# SSRSheet.net
KiCad netlist of a schematic drawn in Altium Designer
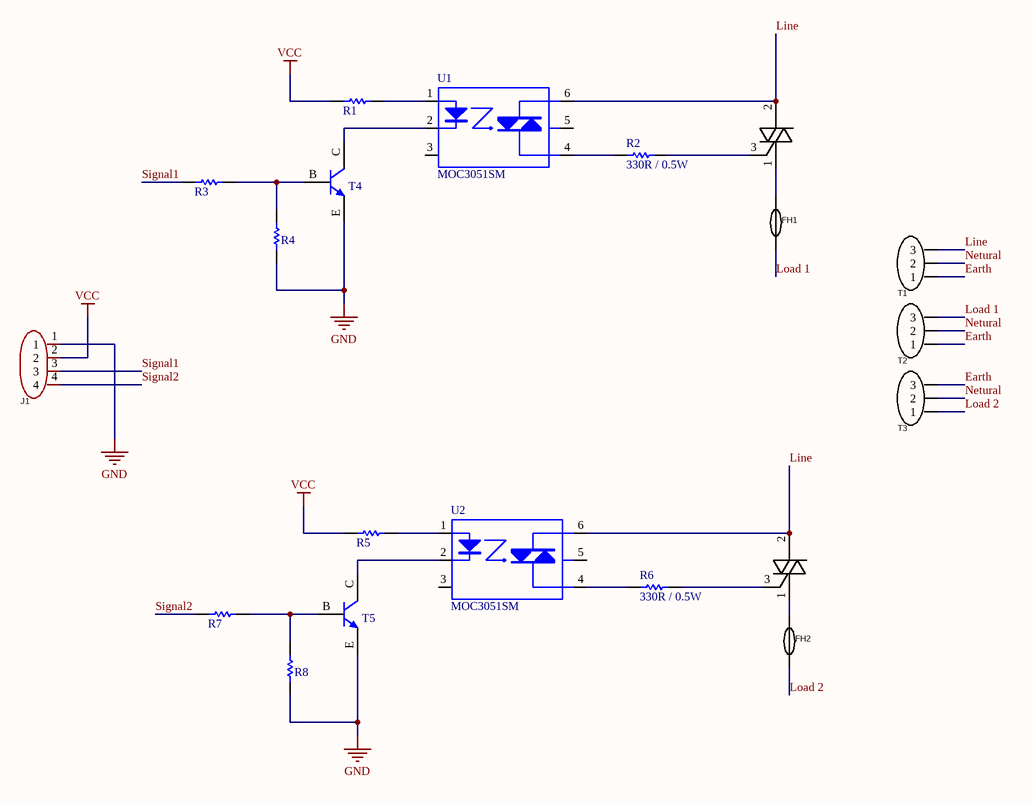
[diagram p0: SSRSheet.SchDoc]

(export (version "E")
  (design (tool "Eeschema 10.0.6"))
  (components
    (comp (ref "FH1")
      (value "XF-154")
      (footprint "FUSE-SMD_L10.5-W5.1")
      (description "C41371861")
      (fields (field (name "MANUFACTURER") "XFCN(兴飞)"))
      (libsource (lib "DIVERSE") (part "XF-154"))
    )
    (comp (ref "FH2")
      (value "XF-154")
      (footprint "FUSE-SMD_L10.5-W5.1")
      (description "C41371861")
      (fields (field (name "MANUFACTURER") "XFCN(兴飞)"))
      (libsource (lib "DIVERSE") (part "XF-154"))
    )
    (comp (ref "J1")
      (value "Header 4P*2mm")
      (footprint "CONN-TH_4P-P2.00_HX20020-4A_2")
      (description "C541313")
      (fields (field (name "MANUFACTURER") "Megastar(兆星)") (field (name "MANUFACTURER PART") "ZX-HY2.0-4PZZ"))
      (libsource (lib "LIB") (part "ZX-HY2.0-4PZZ"))
    )
    (comp (ref "Q1")
      (value "BT136S-800E,118")
      (footprint "TO-252-3_L6.6-W6.1-P4.57-LS9.9-BR-CW")
      (description "C581422")
      (fields (field (name "MANUFACTURER") "WeEn(瑞能)"))
      (libsource (lib "DIVERSE") (part "BT136S-800E,118"))
    )
    (comp (ref "Q2")
      (value "BT136S-800E,118")
      (footprint "TO-252-3_L6.6-W6.1-P4.57-LS9.9-BR-CW")
      (description "C581422")
      (fields (field (name "MANUFACTURER") "WeEn(瑞能)"))
      (libsource (lib "DIVERSE") (part "BT136S-800E,118"))
    )
    (comp (ref "R1")
      (value "330R")
      (footprint "R0402")
      (description "C159971")
      (libsource (lib "DIVERSE") (part "0402 Resistor"))
    )
    (comp (ref "R2")
      (value "330R / 0.5W")
      (footprint "R1210")
      (description "C2933817")
      (fields
        (field (name "MANUFACTURER") "Yageo")
        (field (name "MANUFACTURER PART NUMBER") "AC1210FR-07330RL")
      )
      (libsource (lib "Azan_Lib") (part "AC1210FR-07330RL"))
    )
    (comp (ref "R3")
      (value "4.7kR")
      (footprint "R0402")
      (description "C105871")
      (libsource (lib "DIVERSE") (part "0402 Resistor"))
    )
    (comp (ref "R4")
      (value "10kR")
      (footprint "R0402")
      (description "C60490")
      (libsource (lib "DIVERSE") (part "0402 Resistor"))
    )
    (comp (ref "R5")
      (value "330R")
      (footprint "R0402")
      (description "C159971")
      (libsource (lib "DIVERSE") (part "0402 Resistor"))
    )
    (comp (ref "R6")
      (value "330R / 0.5W")
      (footprint "R1210")
      (description "C2933817")
      (fields
        (field (name "MANUFACTURER") "Yageo")
        (field (name "MANUFACTURER PART NUMBER") "AC1210FR-07330RL")
      )
      (libsource (lib "Azan_Lib") (part "AC1210FR-07330RL"))
    )
    (comp (ref "R7")
      (value "4.7kR")
      (footprint "R0402")
      (description "C105871")
      (libsource (lib "DIVERSE") (part "0402 Resistor"))
    )
    (comp (ref "R8")
      (value "10kR")
      (footprint "R0402")
      (description "C60490")
      (libsource (lib "DIVERSE") (part "0402 Resistor"))
    )
    (comp (ref "T1")
      (value "WJ45C-B-9.5-3P")
      (footprint "CONN-TH_3P-P9.50_WJ45C-B-3P")
      (description "C8442")
      (fields (field (name "MANUFACTURER") "KANGNEX(康奈克斯电气)"))
      (libsource (lib "DIVERSE") (part "WJ45C-B-9.5-3P"))
    )
    (comp (ref "T2")
      (value "WJ45C-B-9.5-3P")
      (footprint "CONN-TH_3P-P9.50_WJ45C-B-3P")
      (description "C8442")
      (fields (field (name "MANUFACTURER") "KANGNEX(康奈克斯电气)"))
      (libsource (lib "DIVERSE") (part "WJ45C-B-9.5-3P"))
    )
    (comp (ref "T3")
      (value "WJ45C-B-9.5-3P")
      (footprint "CONN-TH_3P-P9.50_WJ45C-B-3P")
      (description "C8442")
      (fields (field (name "MANUFACTURER") "KANGNEX(康奈克斯电气)"))
      (libsource (lib "DIVERSE") (part "WJ45C-B-9.5-3P"))
    )
    (comp (ref "T4")
      (value "MMBT3904 Transistor")
      (footprint "MMBT3904")
      (description "C181119")
      (fields (field (name "CREATED BY") "NourAldin"))
      (libsource (lib "MMBT3904 Transistor") (part "MMBT3904 Transistor"))
    )
    (comp (ref "T5")
      (value "MMBT3904 Transistor")
      (footprint "MMBT3904")
      (description "C181119")
      (fields (field (name "CREATED BY") "NourAldin"))
      (libsource (lib "MMBT3904 Transistor") (part "MMBT3904 Transistor"))
    )
    (comp (ref "U1")
      (value "MOC3051SM")
      (footprint "OPTOTRIAC_SMD_6PIN")
      (description "C22373368")
      (fields (field (name "MANUFACTURER") "ON Semiconductor / Fairchild"))
      (libsource (lib "Azan_Lib") (part "MOC3051SM"))
    )
    (comp (ref "U2")
      (value "MOC3051SM")
      (footprint "OPTOTRIAC_SMD_6PIN")
      (description "C22373368")
      (fields (field (name "MANUFACTURER") "ON Semiconductor / Fairchild"))
      (libsource (lib "Azan_Lib") (part "MOC3051SM"))
    )
  )
  (nets
    (net (code "1") (name "/Earth") (class "Default")
      (node (ref "T1") (pin "1") (pinfunction "1_1") (pintype "passive"))
      (node (ref "T2") (pin "1") (pinfunction "1_1") (pintype "passive"))
      (node (ref "T3") (pin "3") (pinfunction "3_3") (pintype "passive"))
    )
    (net (code "2") (name "/Line") (class "Default")
      (node (ref "Q1") (pin "2") (pinfunction "T2_2") (pintype "passive"))
      (node (ref "Q2") (pin "2") (pinfunction "T2_2") (pintype "passive"))
      (node (ref "T1") (pin "3") (pinfunction "3_3") (pintype "passive"))
      (node (ref "U1") (pin "6") (pinfunction "6_6") (pintype "passive"))
      (node (ref "U2") (pin "6") (pinfunction "6_6") (pintype "passive"))
    )
    (net (code "3") (name "/Load 1") (class "Default")
      (node (ref "FH1") (pin "1") (pinfunction "1_1") (pintype "passive"))
      (node (ref "T2") (pin "3") (pinfunction "3_3") (pintype "passive"))
    )
    (net (code "4") (name "/Load 2") (class "Default")
      (node (ref "FH2") (pin "1") (pinfunction "1_1") (pintype "passive"))
      (node (ref "T3") (pin "1") (pinfunction "1_1") (pintype "passive"))
    )
    (net (code "5") (name "/Netural") (class "Default")
      (node (ref "T1") (pin "2") (pinfunction "2_2") (pintype "passive"))
      (node (ref "T2") (pin "2") (pinfunction "2_2") (pintype "passive"))
      (node (ref "T3") (pin "2") (pinfunction "2_2") (pintype "passive"))
    )
    (net (code "6") (name "/Signal1") (class "Default")
      (node (ref "J1") (pin "3") (pinfunction "3_3") (pintype "passive"))
      (node (ref "R3") (pin "1") (pinfunction "1_1") (pintype "passive"))
    )
    (net (code "7") (name "/Signal2") (class "Default")
      (node (ref "J1") (pin "4") (pinfunction "4_4") (pintype "passive"))
      (node (ref "R7") (pin "1") (pinfunction "1_1") (pintype "passive"))
    )
    (net (code "8") (name "GND") (class "Default")
      (node (ref "J1") (pin "1") (pinfunction "1_1") (pintype "passive"))
      (node (ref "R4") (pin "1") (pinfunction "1_1") (pintype "passive"))
      (node (ref "R8") (pin "1") (pinfunction "1_1") (pintype "passive"))
      (node (ref "T4") (pin "E") (pinfunction "E_E") (pintype "passive"))
      (node (ref "T5") (pin "E") (pinfunction "E_E") (pintype "passive"))
    )
    (net (code "9") (name "Net-(Q1-G)") (class "Default")
      (node (ref "Q1") (pin "3") (pinfunction "G_3") (pintype "passive"))
      (node (ref "R2") (pin "1") (pinfunction "1_1") (pintype "passive"))
    )
    (net (code "10") (name "Net-(Q1-T1)") (class "Default")
      (node (ref "FH1") (pin "2") (pinfunction "2_2") (pintype "passive"))
      (node (ref "Q1") (pin "1") (pinfunction "T1_1") (pintype "passive"))
    )
    (net (code "11") (name "Net-(Q2-G)") (class "Default")
      (node (ref "Q2") (pin "3") (pinfunction "G_3") (pintype "passive"))
      (node (ref "R6") (pin "1") (pinfunction "1_1") (pintype "passive"))
    )
    (net (code "12") (name "Net-(Q2-T1)") (class "Default")
      (node (ref "FH2") (pin "2") (pinfunction "2_2") (pintype "passive"))
      (node (ref "Q2") (pin "1") (pinfunction "T1_1") (pintype "passive"))
    )
    (net (code "13") (name "Net-(R1-Pad2)") (class "Default")
      (node (ref "R1") (pin "2") (pinfunction "2_2") (pintype "passive"))
      (node (ref "U1") (pin "1") (pinfunction "1_1") (pintype "passive"))
    )
    (net (code "14") (name "Net-(R2-Pad2)") (class "Default")
      (node (ref "R2") (pin "2") (pinfunction "2_2") (pintype "passive"))
      (node (ref "U1") (pin "4") (pinfunction "4_4") (pintype "passive"))
    )
    (net (code "15") (name "Net-(R3-Pad2)") (class "Default")
      (node (ref "R3") (pin "2") (pinfunction "2_2") (pintype "passive"))
      (node (ref "R4") (pin "2") (pinfunction "2_2") (pintype "passive"))
      (node (ref "T4") (pin "B") (pinfunction "B_B") (pintype "passive"))
    )
    (net (code "16") (name "Net-(R5-Pad2)") (class "Default")
      (node (ref "R5") (pin "2") (pinfunction "2_2") (pintype "passive"))
      (node (ref "U2") (pin "1") (pinfunction "1_1") (pintype "passive"))
    )
    (net (code "17") (name "Net-(R6-Pad2)") (class "Default")
      (node (ref "R6") (pin "2") (pinfunction "2_2") (pintype "passive"))
      (node (ref "U2") (pin "4") (pinfunction "4_4") (pintype "passive"))
    )
    (net (code "18") (name "Net-(R7-Pad2)") (class "Default")
      (node (ref "R7") (pin "2") (pinfunction "2_2") (pintype "passive"))
      (node (ref "R8") (pin "2") (pinfunction "2_2") (pintype "passive"))
      (node (ref "T5") (pin "B") (pinfunction "B_B") (pintype "passive"))
    )
    (net (code "19") (name "Net-(T4-PadC)") (class "Default")
      (node (ref "T4") (pin "C") (pinfunction "C_C") (pintype "passive"))
      (node (ref "U1") (pin "2") (pinfunction "2_2") (pintype "passive"))
    )
    (net (code "20") (name "Net-(T5-PadC)") (class "Default")
      (node (ref "T5") (pin "C") (pinfunction "C_C") (pintype "passive"))
      (node (ref "U2") (pin "2") (pinfunction "2_2") (pintype "passive"))
    )
    (net (code "21") (name "VCC") (class "Default")
      (node (ref "J1") (pin "2") (pinfunction "2_2") (pintype "passive"))
      (node (ref "R1") (pin "1") (pinfunction "1_1") (pintype "passive"))
      (node (ref "R5") (pin "1") (pinfunction "1_1") (pintype "passive"))
    )
    (net (code "22") (name "unconnected-(U1-NC_1-Pad3)") (class "Default")
      (node (ref "U1") (pin "3") (pinfunction "NC_1_3") (pintype "passive"))
    )
    (net (code "23") (name "unconnected-(U1-NC_2-Pad5)") (class "Default")
      (node (ref "U1") (pin "5") (pinfunction "NC_2_5") (pintype "passive"))
    )
    (net (code "24") (name "unconnected-(U2-NC_1-Pad3)") (class "Default")
      (node (ref "U2") (pin "3") (pinfunction "NC_1_3") (pintype "passive"))
    )
    (net (code "25") (name "unconnected-(U2-NC_2-Pad5)") (class "Default")
      (node (ref "U2") (pin "5") (pinfunction "NC_2_5") (pintype "passive"))
    )
  )
)
